# PowerBoard.net
KiCad netlist of a schematic drawn in EAGLE
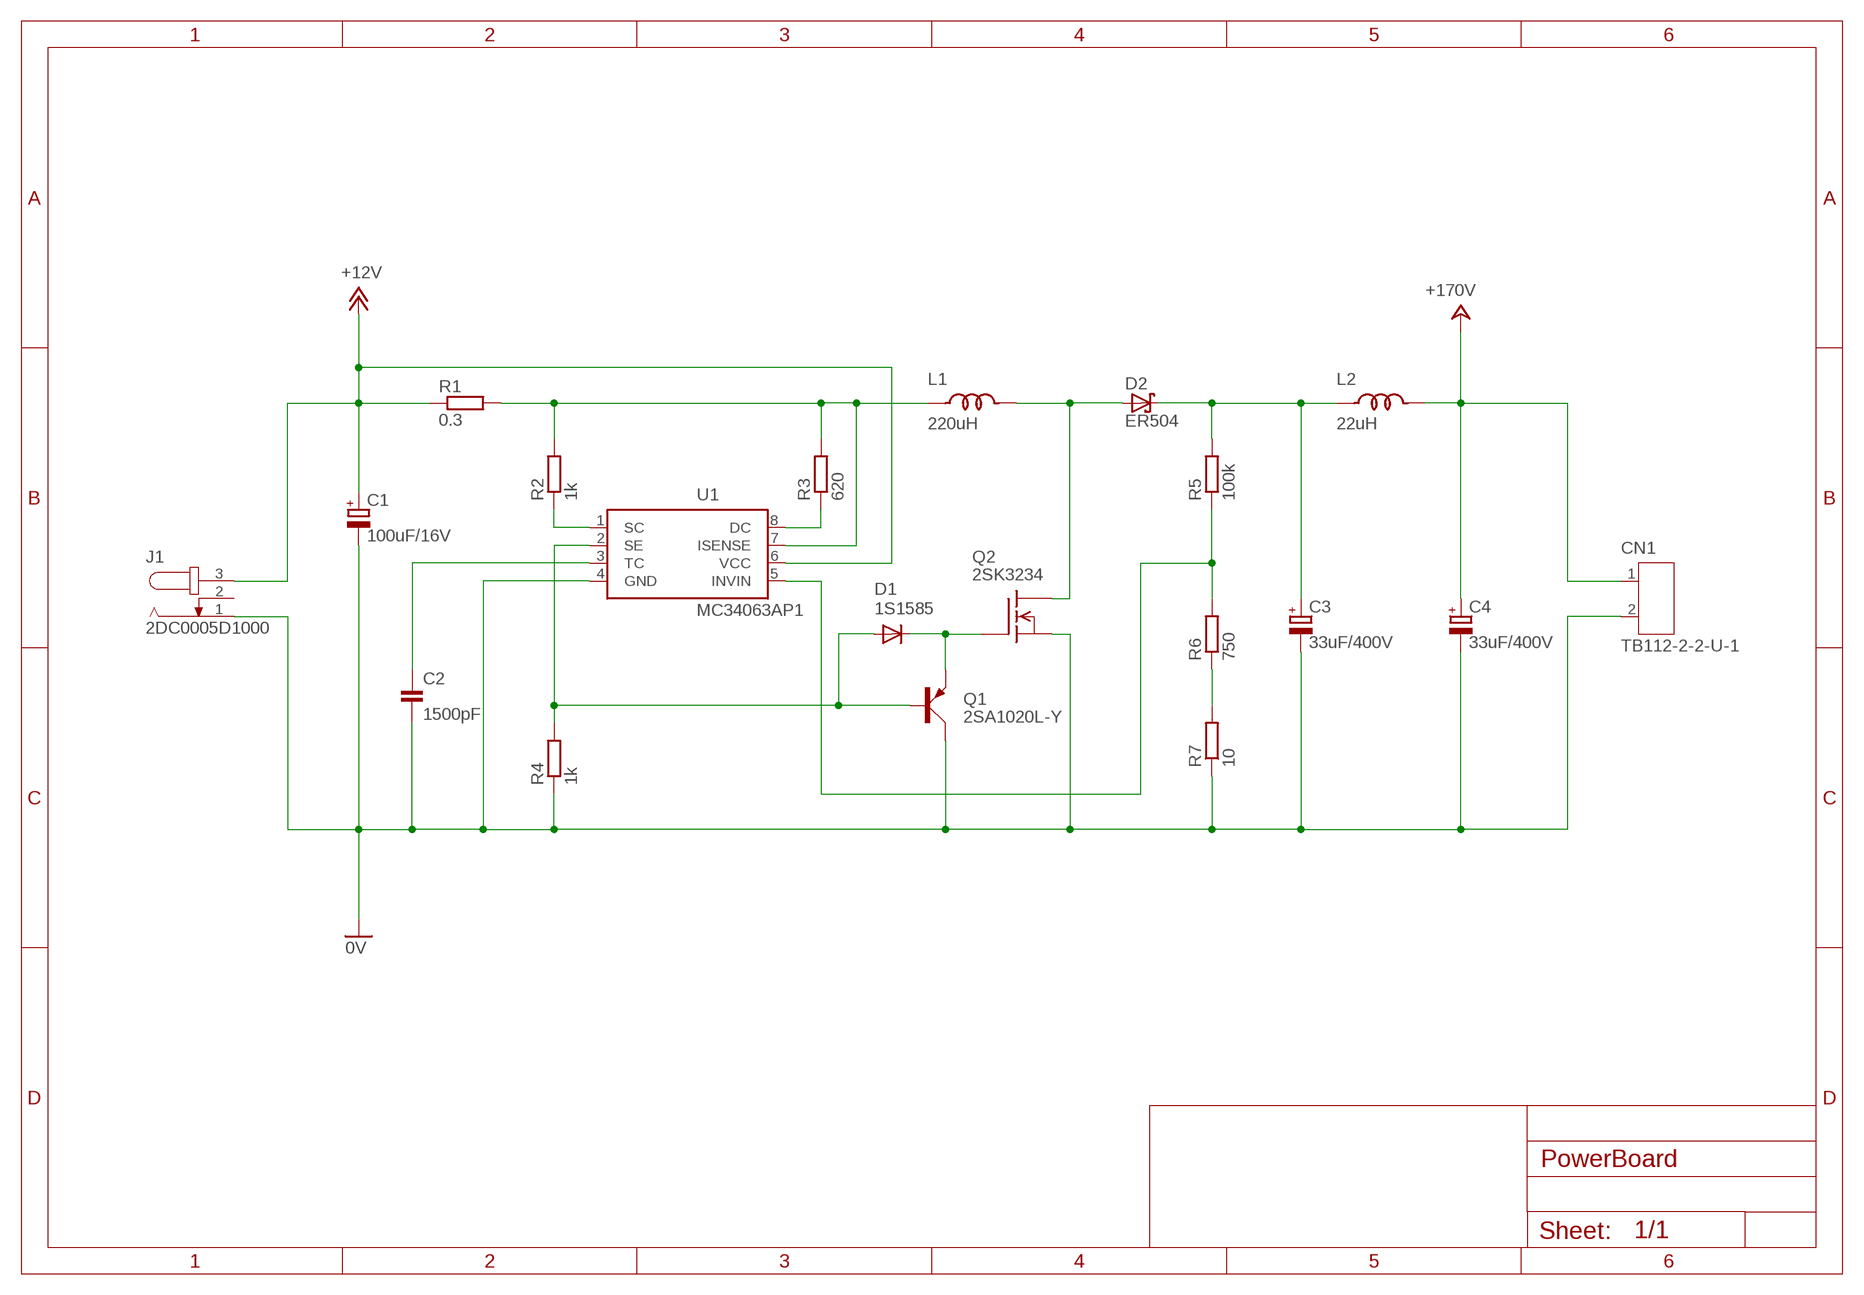
[diagram p0: schematic, sheet 1]

(export (version "E")
  (design (tool "Eeschema 10.0.6"))
  (components
    (comp (ref "C1")
      (value "100uF/16V")
      (footprint "eagle-import:ELECAP_200MIL")
      (libsource (lib "eagle-import") (part "ELECAP_200MIL"))
    )
    (comp (ref "C2")
      (value "1500pF")
      (footprint "eagle-import:CAP_200MIL")
      (libsource (lib "eagle-import") (part "CAP_200MIL"))
    )
    (comp (ref "C3")
      (value "33uF/400V")
      (footprint "eagle-import:ELECAP_300MIL")
      (libsource (lib "eagle-import") (part "ELECAP_300MIL"))
    )
    (comp (ref "C4")
      (value "33uF/400V")
      (footprint "eagle-import:ELECAP_300MIL")
      (libsource (lib "eagle-import") (part "ELECAP_300MIL"))
    )
    (comp (ref "CN1")
      (value "TB112-2-2-U-1")
      (footprint "eagle-import:TERMINAL_BLOCK_2PIN_200MIL")
      (libsource (lib "eagle-import") (part "TB112-2-2-U-1"))
    )
    (comp (ref "D1")
      (value "1S1585")
      (footprint "eagle-import:DIODE-200MIL")
      (libsource (lib "eagle-import") (part "1S1585"))
    )
    (comp (ref "D2")
      (value "ER504")
      (footprint "eagle-import:DIODE-500MIL")
      (libsource (lib "eagle-import") (part "ER504"))
    )
    (comp (ref "J1")
      (value "2DC0005D1000")
      (footprint "eagle-import:DCJACK_2.1_5.5")
      (libsource (lib "eagle-import") (part "2DC0005D1000"))
    )
    (comp (ref "L1")
      (value "220uH")
      (footprint "eagle-import:TOROID_COIL-300MIL")
      (libsource (lib "eagle-import") (part "TC5026-220UH-050"))
    )
    (comp (ref "L2")
      (value "22uH")
      (footprint "eagle-import:TOROID_COIL-300MIL")
      (libsource (lib "eagle-import") (part "TC5026-22UH-060"))
    )
    (comp (ref "Q1")
      (value "2SA1020L-Y")
      (footprint "eagle-import:TO-92NL")
      (libsource (lib "eagle-import") (part "2SA1020L-Y"))
    )
    (comp (ref "Q2")
      (value "2SK3234")
      (footprint "eagle-import:TO-220")
      (libsource (lib "eagle-import") (part "2SK3234"))
    )
    (comp (ref "R1")
      (value "0.3")
      (footprint "eagle-import:RESISTOR_0411_600MIL")
      (libsource (lib "eagle-import") (part "RESISTOR_600MIL"))
    )
    (comp (ref "R2")
      (value "1k")
      (footprint "eagle-import:RESISTOR_0411_600MIL")
      (libsource (lib "eagle-import") (part "RESISTOR_600MIL"))
    )
    (comp (ref "R3")
      (value "620")
      (footprint "eagle-import:RESISTOR_0411_600MIL")
      (libsource (lib "eagle-import") (part "RESISTOR_600MIL"))
    )
    (comp (ref "R4")
      (value "1k")
      (footprint "eagle-import:RESISTOR_0411_600MIL")
      (libsource (lib "eagle-import") (part "RESISTOR_600MIL"))
    )
    (comp (ref "R5")
      (value "100k")
      (footprint "eagle-import:RESISTOR_0411_600MIL")
      (libsource (lib "eagle-import") (part "RESISTOR_600MIL"))
    )
    (comp (ref "R6")
      (value "750")
      (footprint "eagle-import:RESISTOR_0411_600MIL")
      (libsource (lib "eagle-import") (part "RESISTOR_600MIL"))
    )
    (comp (ref "R7")
      (value "10")
      (footprint "eagle-import:RESISTOR_0411_600MIL")
      (libsource (lib "eagle-import") (part "RESISTOR_600MIL"))
    )
    (comp (ref "U1")
      (value "MC34063AP1")
      (footprint "eagle-import:DIL08")
      (libsource (lib "eagle-import") (part "MC34063AP1"))
    )
  )
  (nets
    (net (code "1") (name "+12V") (class "Default")
      (node (ref "C1") (pin "+") (pinfunction "+_+") (pintype "passive"))
      (node (ref "J1") (pin "3") (pinfunction "3_3") (pintype "passive"))
      (node (ref "R1") (pin "1") (pinfunction "1_1") (pintype "passive"))
      (node (ref "U1") (pin "6") (pinfunction "VCC_6") (pintype "passive"))
    )
    (net (code "2") (name "+170V") (class "Default")
      (node (ref "C4") (pin "+") (pinfunction "+_+") (pintype "passive"))
      (node (ref "CN1") (pin "1") (pinfunction "1_1") (pintype "passive"))
      (node (ref "L2") (pin "2") (pinfunction "2_2") (pintype "passive"))
    )
    (net (code "3") (name "0V") (class "Default")
      (node (ref "C1") (pin "-") (pinfunction "-_-") (pintype "passive"))
      (node (ref "C2") (pin "2") (pinfunction "2_2") (pintype "passive"))
      (node (ref "C3") (pin "-") (pinfunction "-_-") (pintype "passive"))
      (node (ref "C4") (pin "-") (pinfunction "-_-") (pintype "passive"))
      (node (ref "CN1") (pin "2") (pinfunction "2_2") (pintype "passive"))
      (node (ref "J1") (pin "1") (pinfunction "1_1") (pintype "passive"))
      (node (ref "Q1") (pin "2") (pinfunction "C_2") (pintype "passive"))
      (node (ref "Q2") (pin "3") (pinfunction "S_3") (pintype "passive"))
      (node (ref "R4") (pin "1") (pinfunction "1_1") (pintype "passive"))
      (node (ref "R7") (pin "1") (pinfunction "1_1") (pintype "passive"))
      (node (ref "U1") (pin "4") (pinfunction "GND_4") (pintype "passive"))
    )
    (net (code "4") (name "Net-(C3-Pad+)") (class "Default")
      (node (ref "C3") (pin "+") (pinfunction "+_+") (pintype "passive"))
      (node (ref "D2") (pin "C") (pinfunction "C_C") (pintype "passive"))
      (node (ref "L2") (pin "1") (pinfunction "1_1") (pintype "passive"))
      (node (ref "R5") (pin "2") (pinfunction "2_2") (pintype "passive"))
    )
    (net (code "5") (name "Net-(Q1-B)") (class "Default")
      (node (ref "D1") (pin "A") (pinfunction "A_A") (pintype "passive"))
      (node (ref "Q1") (pin "3") (pinfunction "B_3") (pintype "passive"))
      (node (ref "R4") (pin "2") (pinfunction "2_2") (pintype "passive"))
      (node (ref "U1") (pin "2") (pinfunction "SE_2") (pintype "passive"))
    )
    (net (code "6") (name "Net-(Q1-E)") (class "Default")
      (node (ref "D1") (pin "C") (pinfunction "C_C") (pintype "passive"))
      (node (ref "Q1") (pin "1") (pinfunction "E_1") (pintype "passive"))
      (node (ref "Q2") (pin "1") (pinfunction "G_1") (pintype "passive"))
    )
    (net (code "7") (name "Net-(Q2-D)") (class "Default")
      (node (ref "D2") (pin "A") (pinfunction "A_A") (pintype "passive"))
      (node (ref "L1") (pin "2") (pinfunction "2_2") (pintype "passive"))
      (node (ref "Q2") (pin "2") (pinfunction "D_2") (pintype "passive"))
    )
    (net (code "8") (name "Net-(R6-Pad1)") (class "Default")
      (node (ref "R6") (pin "1") (pinfunction "1_1") (pintype "passive"))
      (node (ref "R7") (pin "2") (pinfunction "2_2") (pintype "passive"))
    )
    (net (code "9") (name "Net-(U1-DC)") (class "Default")
      (node (ref "R3") (pin "1") (pinfunction "1_1") (pintype "passive"))
      (node (ref "U1") (pin "8") (pinfunction "DC_8") (pintype "passive"))
    )
    (net (code "10") (name "Net-(U1-INVIN)") (class "Default")
      (node (ref "R5") (pin "1") (pinfunction "1_1") (pintype "passive"))
      (node (ref "R6") (pin "2") (pinfunction "2_2") (pintype "passive"))
      (node (ref "U1") (pin "5") (pinfunction "INVIN_5") (pintype "passive"))
    )
    (net (code "11") (name "Net-(U1-ISENSE)") (class "Default")
      (node (ref "L1") (pin "1") (pinfunction "1_1") (pintype "passive"))
      (node (ref "R1") (pin "2") (pinfunction "2_2") (pintype "passive"))
      (node (ref "R2") (pin "2") (pinfunction "2_2") (pintype "passive"))
      (node (ref "R3") (pin "2") (pinfunction "2_2") (pintype "passive"))
      (node (ref "U1") (pin "7") (pinfunction "ISENSE_7") (pintype "passive"))
    )
    (net (code "12") (name "Net-(U1-SC)") (class "Default")
      (node (ref "R2") (pin "1") (pinfunction "1_1") (pintype "passive"))
      (node (ref "U1") (pin "1") (pinfunction "SC_1") (pintype "passive"))
    )
    (net (code "13") (name "Net-(U1-TC)") (class "Default")
      (node (ref "C2") (pin "1") (pinfunction "1_1") (pintype "passive"))
      (node (ref "U1") (pin "3") (pinfunction "TC_3") (pintype "passive"))
    )
    (net (code "14") (name "unconnected-(J1-Pad2)") (class "Default")
      (node (ref "J1") (pin "2") (pinfunction "2_2") (pintype "passive"))
    )
  )
)
